# cosv-carrier-teensy40_old.net
KiCad netlist of a schematic drawn in EAGLE
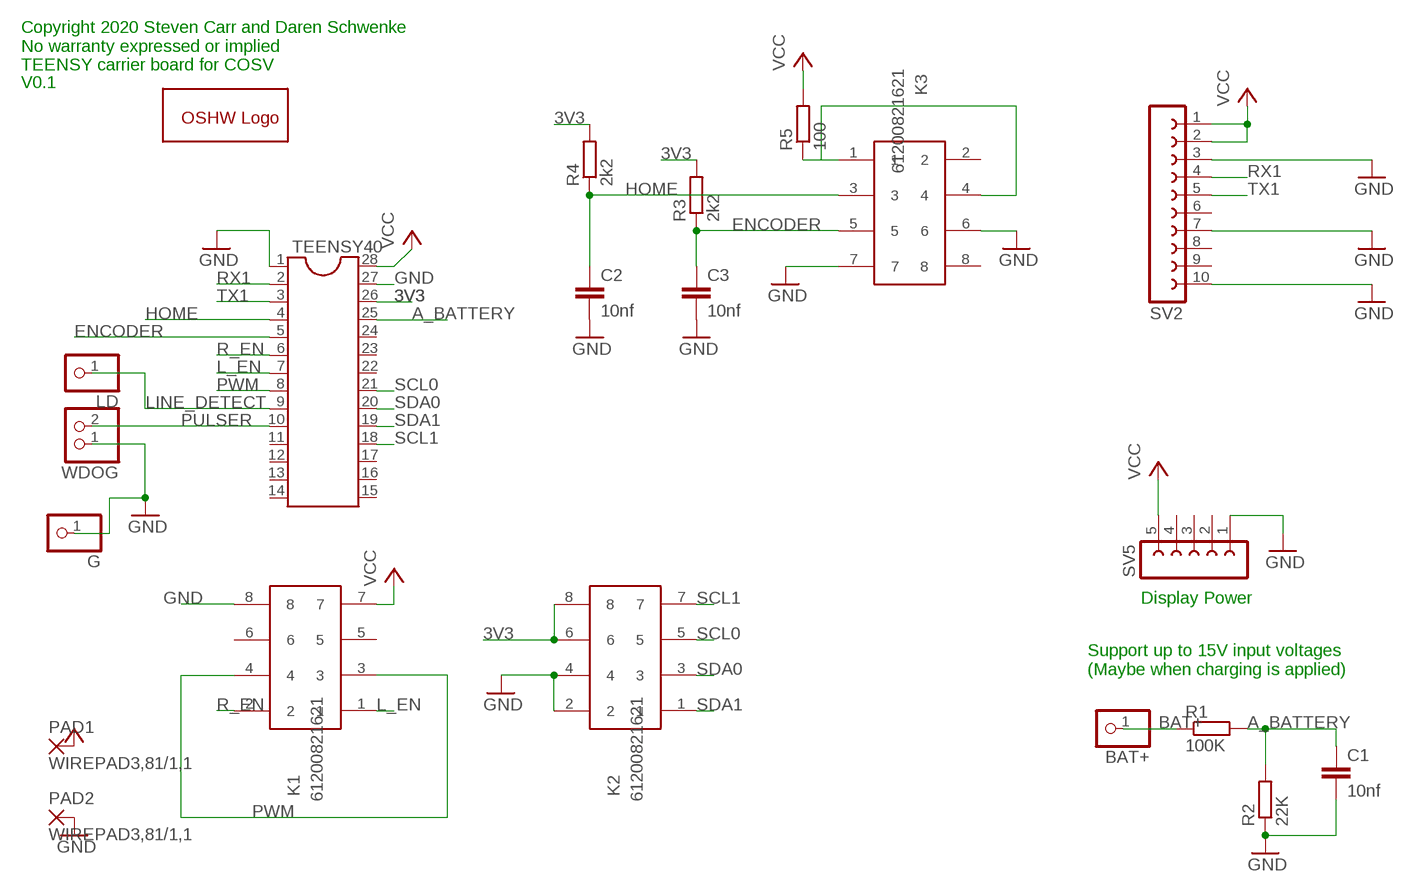
[diagram p0: schematic, sheet 1]

(export (version "E")
  (design (tool "Eeschema 10.0.6"))
  (components
    (comp (ref "BAT+")
      (value "PINHD-1X01_2.54-S")
      (footprint "eagle-import:1X01-S")
      (libsource (lib "eagle-import") (part "PINHD-1X01_2.54-S"))
    )
    (comp (ref "C1")
      (value "10nf")
      (footprint "eagle-import:C1206")
      (libsource (lib "eagle-import") (part "C-EUC1206"))
    )
    (comp (ref "C2")
      (value "10nf")
      (footprint "eagle-import:C1206")
      (libsource (lib "eagle-import") (part "C-EUC1206"))
    )
    (comp (ref "C3")
      (value "10nf")
      (footprint "eagle-import:C1206")
      (libsource (lib "eagle-import") (part "C-EUC1206"))
    )
    (comp (ref "G")
      (value "PINHD-1X01_2.54-S")
      (footprint "eagle-import:1X01-S")
      (libsource (lib "eagle-import") (part "PINHD-1X01_2.54-S"))
    )
    (comp (ref "GOLD_ORB_SM1")
      (value "OSHWLOGOLOGO8MM")
      (footprint "eagle-import:OSHW_8MM")
      (libsource (lib "eagle-import") (part "OSHWLOGOLOGO8MM"))
    )
    (comp (ref "K1")
      (value "61200821621")
      (footprint "eagle-import:61200821621")
      (libsource (lib "eagle-import") (part "61200821621"))
    )
    (comp (ref "K2")
      (value "61200821621")
      (footprint "eagle-import:61200821621")
      (libsource (lib "eagle-import") (part "61200821621"))
    )
    (comp (ref "K3")
      (value "61200821621")
      (footprint "eagle-import:61200821621")
      (libsource (lib "eagle-import") (part "61200821621"))
    )
    (comp (ref "LD")
      (value "PINHD-1X01_2.54-S")
      (footprint "eagle-import:1X01-S")
      (libsource (lib "eagle-import") (part "PINHD-1X01_2.54-S"))
    )
    (comp (ref "PAD1")
      (value "WIREPAD3,81/1,1")
      (footprint "eagle-import:3,81_1,1")
      (libsource (lib "eagle-import") (part "WIREPAD3,81/1,1"))
    )
    (comp (ref "PAD2")
      (value "WIREPAD3,81/1,1")
      (footprint "eagle-import:3,81_1,1")
      (libsource (lib "eagle-import") (part "WIREPAD3,81/1,1"))
    )
    (comp (ref "R1")
      (value "100K")
      (footprint "eagle-import:R1206")
      (libsource (lib "eagle-import") (part "R-EU_R1206"))
    )
    (comp (ref "R2")
      (value "22K")
      (footprint "eagle-import:R1206")
      (libsource (lib "eagle-import") (part "R-EU_R1206"))
    )
    (comp (ref "R3")
      (value "2k2")
      (footprint "eagle-import:R1206")
      (libsource (lib "eagle-import") (part "R-EU_R1206"))
    )
    (comp (ref "R4")
      (value "2k2")
      (footprint "eagle-import:R1206")
      (libsource (lib "eagle-import") (part "R-EU_R1206"))
    )
    (comp (ref "R5")
      (value "100")
      (footprint "eagle-import:R1206")
      (libsource (lib "eagle-import") (part "R-EU_R1206"))
    )
    (comp (ref "SV2")
      (value "FE10-1")
      (footprint "eagle-import:FE10")
      (libsource (lib "eagle-import") (part "FE10-1"))
    )
    (comp (ref "SV5")
      (value "FE05W")
      (footprint "eagle-import:FE05W")
      (libsource (lib "eagle-import") (part "FE05W"))
    )
    (comp (ref "TEENSY40")
      (value "DIL28")
      (footprint "eagle-import:DIL28-6")
      (libsource (lib "eagle-import") (part "DIL28"))
    )
    (comp (ref "WDOG")
      (value "PINHD-1X2")
      (footprint "eagle-import:1X02")
      (libsource (lib "eagle-import") (part "PINHD-1X2"))
    )
  )
  (nets
    (net (code "1") (name "/3V3") (class "Default")
      (node (ref "K2") (pin "6") (pinfunction "6_6") (pintype "passive"))
      (node (ref "K2") (pin "8") (pinfunction "8_8") (pintype "passive"))
      (node (ref "R3") (pin "2") (pinfunction "2_2") (pintype "passive"))
      (node (ref "R4") (pin "2") (pinfunction "2_2") (pintype "passive"))
      (node (ref "TEENSY40") (pin "26") (pinfunction "26_26") (pintype "passive"))
    )
    (net (code "2") (name "/A_BATTERY") (class "Default")
      (node (ref "C1") (pin "1") (pinfunction "1_1") (pintype "passive"))
      (node (ref "R1") (pin "2") (pinfunction "2_2") (pintype "passive"))
      (node (ref "R2") (pin "2") (pinfunction "2_2") (pintype "passive"))
      (node (ref "TEENSY40") (pin "25") (pinfunction "25_25") (pintype "passive"))
    )
    (net (code "3") (name "/BAT+") (class "Default")
      (node (ref "BAT+") (pin "1") (pinfunction "1_1") (pintype "passive"))
      (node (ref "R1") (pin "1") (pinfunction "1_1") (pintype "passive"))
    )
    (net (code "4") (name "/ENCODER") (class "Default")
      (node (ref "C3") (pin "1") (pinfunction "1_1") (pintype "passive"))
      (node (ref "K3") (pin "5") (pinfunction "5_5") (pintype "passive"))
      (node (ref "R3") (pin "1") (pinfunction "1_1") (pintype "passive"))
      (node (ref "TEENSY40") (pin "5") (pinfunction "5_5") (pintype "passive"))
    )
    (net (code "5") (name "/HOME") (class "Default")
      (node (ref "C2") (pin "1") (pinfunction "1_1") (pintype "passive"))
      (node (ref "K3") (pin "3") (pinfunction "3_3") (pintype "passive"))
      (node (ref "R4") (pin "1") (pinfunction "1_1") (pintype "passive"))
      (node (ref "TEENSY40") (pin "4") (pinfunction "4_4") (pintype "passive"))
    )
    (net (code "6") (name "/LINE_DETECT") (class "Default")
      (node (ref "LD") (pin "1") (pinfunction "1_1") (pintype "passive"))
      (node (ref "TEENSY40") (pin "9") (pinfunction "9_9") (pintype "passive"))
    )
    (net (code "7") (name "/L_EN") (class "Default")
      (node (ref "K1") (pin "1") (pinfunction "1_1") (pintype "passive"))
      (node (ref "TEENSY40") (pin "7") (pinfunction "7_7") (pintype "passive"))
    )
    (net (code "8") (name "/PULSER") (class "Default")
      (node (ref "TEENSY40") (pin "10") (pinfunction "10_10") (pintype "passive"))
      (node (ref "WDOG") (pin "2") (pinfunction "2_2") (pintype "passive"))
    )
    (net (code "9") (name "/PWM") (class "Default")
      (node (ref "K1") (pin "3") (pinfunction "3_3") (pintype "passive"))
      (node (ref "K1") (pin "4") (pinfunction "4_4") (pintype "passive"))
      (node (ref "TEENSY40") (pin "8") (pinfunction "8_8") (pintype "passive"))
    )
    (net (code "10") (name "/RX1") (class "Default")
      (node (ref "SV2") (pin "4") (pinfunction "4_4") (pintype "passive"))
      (node (ref "TEENSY40") (pin "2") (pinfunction "2_2") (pintype "passive"))
    )
    (net (code "11") (name "/R_EN") (class "Default")
      (node (ref "K1") (pin "2") (pinfunction "2_2") (pintype "passive"))
      (node (ref "TEENSY40") (pin "6") (pinfunction "6_6") (pintype "passive"))
    )
    (net (code "12") (name "/SCL0") (class "Default")
      (node (ref "K2") (pin "5") (pinfunction "5_5") (pintype "passive"))
      (node (ref "TEENSY40") (pin "21") (pinfunction "21_21") (pintype "passive"))
    )
    (net (code "13") (name "/SCL1") (class "Default")
      (node (ref "K2") (pin "7") (pinfunction "7_7") (pintype "passive"))
      (node (ref "TEENSY40") (pin "18") (pinfunction "18_18") (pintype "passive"))
    )
    (net (code "14") (name "/SDA0") (class "Default")
      (node (ref "K2") (pin "3") (pinfunction "3_3") (pintype "passive"))
      (node (ref "TEENSY40") (pin "20") (pinfunction "20_20") (pintype "passive"))
    )
    (net (code "15") (name "/SDA1") (class "Default")
      (node (ref "K2") (pin "1") (pinfunction "1_1") (pintype "passive"))
      (node (ref "TEENSY40") (pin "19") (pinfunction "19_19") (pintype "passive"))
    )
    (net (code "16") (name "/TX1") (class "Default")
      (node (ref "SV2") (pin "5") (pinfunction "5_5") (pintype "passive"))
      (node (ref "TEENSY40") (pin "3") (pinfunction "3_3") (pintype "passive"))
    )
    (net (code "17") (name "GND") (class "Default")
      (node (ref "C1") (pin "2") (pinfunction "2_2") (pintype "passive"))
      (node (ref "C2") (pin "2") (pinfunction "2_2") (pintype "passive"))
      (node (ref "C3") (pin "2") (pinfunction "2_2") (pintype "passive"))
      (node (ref "G") (pin "1") (pinfunction "1_1") (pintype "passive"))
      (node (ref "K1") (pin "8") (pinfunction "8_8") (pintype "passive"))
      (node (ref "K2") (pin "2") (pinfunction "2_2") (pintype "passive"))
      (node (ref "K2") (pin "4") (pinfunction "4_4") (pintype "passive"))
      (node (ref "K3") (pin "6") (pinfunction "6_6") (pintype "passive"))
      (node (ref "K3") (pin "7") (pinfunction "7_7") (pintype "passive"))
      (node (ref "PAD2") (pin "1") (pinfunction "P_1") (pintype "passive"))
      (node (ref "R2") (pin "1") (pinfunction "1_1") (pintype "passive"))
      (node (ref "SV2") (pin "10") (pinfunction "10_10") (pintype "passive"))
      (node (ref "SV2") (pin "3") (pinfunction "3_3") (pintype "passive"))
      (node (ref "SV2") (pin "7") (pinfunction "7_7") (pintype "passive"))
      (node (ref "SV5") (pin "1") (pinfunction "1_1") (pintype "passive"))
      (node (ref "TEENSY40") (pin "1") (pinfunction "1_1") (pintype "passive"))
      (node (ref "TEENSY40") (pin "27") (pinfunction "27_27") (pintype "passive"))
      (node (ref "WDOG") (pin "1") (pinfunction "1_1") (pintype "passive"))
    )
    (net (code "18") (name "Net-(K3-Pad1)") (class "Default")
      (node (ref "K3") (pin "1") (pinfunction "1_1") (pintype "passive"))
      (node (ref "K3") (pin "4") (pinfunction "4_4") (pintype "passive"))
      (node (ref "R5") (pin "1") (pinfunction "1_1") (pintype "passive"))
    )
    (net (code "19") (name "VCC") (class "Default")
      (node (ref "K1") (pin "7") (pinfunction "7_7") (pintype "passive"))
      (node (ref "PAD1") (pin "1") (pinfunction "P_1") (pintype "passive"))
      (node (ref "R5") (pin "2") (pinfunction "2_2") (pintype "passive"))
      (node (ref "SV2") (pin "1") (pinfunction "1_1") (pintype "passive"))
      (node (ref "SV2") (pin "2") (pinfunction "2_2") (pintype "passive"))
      (node (ref "SV5") (pin "5") (pinfunction "5_5") (pintype "passive"))
      (node (ref "TEENSY40") (pin "28") (pinfunction "28_28") (pintype "passive"))
    )
    (net (code "20") (name "unconnected-(K1-Pad5)") (class "Default")
      (node (ref "K1") (pin "5") (pinfunction "5_5") (pintype "passive"))
    )
    (net (code "21") (name "unconnected-(K1-Pad6)") (class "Default")
      (node (ref "K1") (pin "6") (pinfunction "6_6") (pintype "passive"))
    )
    (net (code "22") (name "unconnected-(K3-Pad2)") (class "Default")
      (node (ref "K3") (pin "2") (pinfunction "2_2") (pintype "passive"))
    )
    (net (code "23") (name "unconnected-(K3-Pad8)") (class "Default")
      (node (ref "K3") (pin "8") (pinfunction "8_8") (pintype "passive"))
    )
    (net (code "24") (name "unconnected-(SV2-Pad6)") (class "Default")
      (node (ref "SV2") (pin "6") (pinfunction "6_6") (pintype "passive"))
    )
    (net (code "25") (name "unconnected-(SV2-Pad8)") (class "Default")
      (node (ref "SV2") (pin "8") (pinfunction "8_8") (pintype "passive"))
    )
    (net (code "26") (name "unconnected-(SV2-Pad9)") (class "Default")
      (node (ref "SV2") (pin "9") (pinfunction "9_9") (pintype "passive"))
    )
    (net (code "27") (name "unconnected-(SV5-Pad2)") (class "Default")
      (node (ref "SV5") (pin "2") (pinfunction "2_2") (pintype "passive"))
    )
    (net (code "28") (name "unconnected-(SV5-Pad3)") (class "Default")
      (node (ref "SV5") (pin "3") (pinfunction "3_3") (pintype "passive"))
    )
    (net (code "29") (name "unconnected-(SV5-Pad4)") (class "Default")
      (node (ref "SV5") (pin "4") (pinfunction "4_4") (pintype "passive"))
    )
    (net (code "30") (name "unconnected-(TEENSY40-Pad11)") (class "Default")
      (node (ref "TEENSY40") (pin "11") (pinfunction "11_11") (pintype "passive"))
    )
    (net (code "31") (name "unconnected-(TEENSY40-Pad12)") (class "Default")
      (node (ref "TEENSY40") (pin "12") (pinfunction "12_12") (pintype "passive"))
    )
    (net (code "32") (name "unconnected-(TEENSY40-Pad13)") (class "Default")
      (node (ref "TEENSY40") (pin "13") (pinfunction "13_13") (pintype "passive"))
    )
    (net (code "33") (name "unconnected-(TEENSY40-Pad14)") (class "Default")
      (node (ref "TEENSY40") (pin "14") (pinfunction "14_14") (pintype "passive"))
    )
    (net (code "34") (name "unconnected-(TEENSY40-Pad15)") (class "Default")
      (node (ref "TEENSY40") (pin "15") (pinfunction "15_15") (pintype "passive"))
    )
    (net (code "35") (name "unconnected-(TEENSY40-Pad16)") (class "Default")
      (node (ref "TEENSY40") (pin "16") (pinfunction "16_16") (pintype "passive"))
    )
    (net (code "36") (name "unconnected-(TEENSY40-Pad17)") (class "Default")
      (node (ref "TEENSY40") (pin "17") (pinfunction "17_17") (pintype "passive"))
    )
    (net (code "37") (name "unconnected-(TEENSY40-Pad22)") (class "Default")
      (node (ref "TEENSY40") (pin "22") (pinfunction "22_22") (pintype "passive"))
    )
    (net (code "38") (name "unconnected-(TEENSY40-Pad23)") (class "Default")
      (node (ref "TEENSY40") (pin "23") (pinfunction "23_23") (pintype "passive"))
    )
    (net (code "39") (name "unconnected-(TEENSY40-Pad24)") (class "Default")
      (node (ref "TEENSY40") (pin "24") (pinfunction "24_24") (pintype "passive"))
    )
  )
)
